# LightBoard2.net
KiCad netlist of a schematic drawn in EAGLE
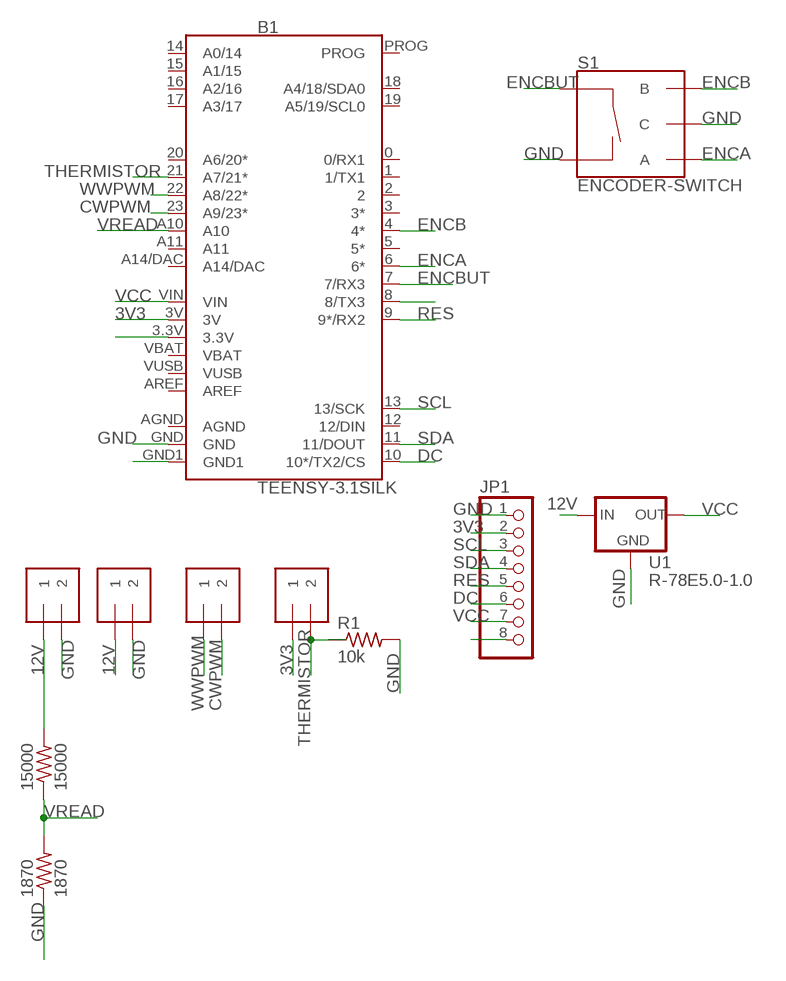
[diagram p0: schematic, sheet 1]

(export (version "E")
  (design (tool "Eeschema 10.0.6"))
  (components
    (comp (ref "1870")
      (value "1870")
      (footprint "eagle-import:0204_5")
      (libsource (lib "eagle-import") (part "R-US_0204/5"))
    )
    (comp (ref "15000")
      (value "15000")
      (footprint "eagle-import:0204_5")
      (libsource (lib "eagle-import") (part "R-US_0204/5"))
    )
    (comp (ref "B1")
      (value "TEENSY-3.1SILK")
      (footprint "eagle-import:TEENSY-3.1")
      (libsource (lib "eagle-import") (part "TEENSY-3.1SILK"))
    )
    (comp (ref "J1")
      (value "1X2-3.5MM")
      (footprint "eagle-import:1X2-3.5MM")
      (libsource (lib "eagle-import") (part "1X2-3.5MM"))
    )
    (comp (ref "J2")
      (value "1X2-3.5MM")
      (footprint "eagle-import:1X2-3.5MM")
      (libsource (lib "eagle-import") (part "1X2-3.5MM"))
    )
    (comp (ref "J3")
      (value "1X2-3.5MM")
      (footprint "eagle-import:1X2-3.5MM")
      (libsource (lib "eagle-import") (part "1X2-3.5MM"))
    )
    (comp (ref "J5")
      (value "1X2-3.5MM")
      (footprint "eagle-import:1X2-3.5MM")
      (libsource (lib "eagle-import") (part "1X2-3.5MM"))
    )
    (comp (ref "JP1")
      (value "PINHD-1X8LOCK")
      (footprint "eagle-import:1X08-LOCK")
      (libsource (lib "eagle-import") (part "PINHD-1X8LOCK"))
    )
    (comp (ref "R1")
      (value "10k")
      (footprint "eagle-import:0204_5")
      (libsource (lib "eagle-import") (part "R-US_0204/5"))
    )
    (comp (ref "S1")
      (value "ENCODER-SWITCH")
      (footprint "eagle-import:ROTARY_ENC_PLAIN")
      (libsource (lib "eagle-import") (part "ENCODER-SWITCH"))
    )
    (comp (ref "U1")
      (value "R-78E5.0-1.0")
      (footprint "eagle-import:DC-DC_CONVERTER_78XX")
      (libsource (lib "eagle-import") (part "R-78E5.0-1.0"))
    )
  )
  (nets
    (net (code "1") (name "/3V3") (class "Default")
      (node (ref "B1") (pin "3V") (pinfunction "3V_3V") (pintype "power_in"))
      (node (ref "J3") (pin "1") (pinfunction "1_1") (pintype "passive"))
      (node (ref "JP1") (pin "2") (pinfunction "2_2") (pintype "passive"))
    )
    (net (code "2") (name "/12V") (class "Default")
      (node (ref "15000") (pin "2") (pinfunction "2_2") (pintype "passive"))
      (node (ref "J2") (pin "1") (pinfunction "1_1") (pintype "passive"))
      (node (ref "J5") (pin "1") (pinfunction "1_1") (pintype "passive"))
      (node (ref "U1") (pin "VIN") (pinfunction "IN_VIN") (pintype "input"))
    )
    (net (code "3") (name "/AGND") (class "Default")
      (node (ref "B1") (pin "AGND") (pinfunction "AGND_AGND") (pintype "power_in"))
    )
    (net (code "4") (name "/CWPWM") (class "Default")
      (node (ref "B1") (pin "23") (pinfunction "A9/23*_23") (pintype "bidirectional"))
      (node (ref "J1") (pin "2") (pinfunction "2_2") (pintype "passive"))
    )
    (net (code "5") (name "/DC") (class "Default")
      (node (ref "B1") (pin "10") (pinfunction "10*/TX2/CS_10") (pintype "bidirectional"))
      (node (ref "JP1") (pin "6") (pinfunction "6_6") (pintype "passive"))
    )
    (net (code "6") (name "/ENCA") (class "Default")
      (node (ref "B1") (pin "6") (pinfunction "6*_6") (pintype "bidirectional"))
      (node (ref "S1") (pin "A") (pinfunction "A_A") (pintype "bidirectional"))
    )
    (net (code "7") (name "/ENCB") (class "Default")
      (node (ref "B1") (pin "4") (pinfunction "4*_4") (pintype "bidirectional"))
      (node (ref "S1") (pin "B") (pinfunction "B_B") (pintype "bidirectional"))
    )
    (net (code "8") (name "/ENCBUT") (class "Default")
      (node (ref "B1") (pin "7") (pinfunction "7/RX3_7") (pintype "bidirectional"))
      (node (ref "S1") (pin "SW+") (pinfunction "SW+_SW+") (pintype "bidirectional"))
    )
    (net (code "9") (name "/GND") (class "Default")
      (node (ref "1870") (pin "1") (pinfunction "1_1") (pintype "passive"))
      (node (ref "B1") (pin "GND") (pinfunction "GND_GND") (pintype "power_in"))
      (node (ref "B1") (pin "GND1") (pinfunction "GND1_GND1") (pintype "power_in"))
      (node (ref "J2") (pin "2") (pinfunction "2_2") (pintype "passive"))
      (node (ref "J5") (pin "2") (pinfunction "2_2") (pintype "passive"))
      (node (ref "JP1") (pin "1") (pinfunction "1_1") (pintype "passive"))
      (node (ref "R1") (pin "2") (pinfunction "2_2") (pintype "passive"))
      (node (ref "S1") (pin "C") (pinfunction "C_C") (pintype "bidirectional"))
      (node (ref "S1") (pin "SW-") (pinfunction "SW-_SW-") (pintype "bidirectional"))
      (node (ref "U1") (pin "GND") (pinfunction "GND_GND") (pintype "input"))
    )
    (net (code "10") (name "/RES") (class "Default")
      (node (ref "B1") (pin "9") (pinfunction "9*/RX2_9") (pintype "bidirectional"))
      (node (ref "JP1") (pin "5") (pinfunction "5_5") (pintype "passive"))
    )
    (net (code "11") (name "/SCL") (class "Default")
      (node (ref "B1") (pin "13") (pinfunction "13/SCK_13") (pintype "bidirectional"))
      (node (ref "JP1") (pin "3") (pinfunction "3_3") (pintype "passive"))
    )
    (net (code "12") (name "/SDA") (class "Default")
      (node (ref "B1") (pin "11") (pinfunction "11/DOUT_11") (pintype "bidirectional"))
      (node (ref "JP1") (pin "4") (pinfunction "4_4") (pintype "passive"))
    )
    (net (code "13") (name "/THERMISTOR") (class "Default")
      (node (ref "B1") (pin "21") (pinfunction "A7/21*_21") (pintype "bidirectional"))
      (node (ref "J3") (pin "2") (pinfunction "2_2") (pintype "passive"))
      (node (ref "R1") (pin "1") (pinfunction "1_1") (pintype "passive"))
    )
    (net (code "14") (name "/VBAT") (class "Default")
      (node (ref "B1") (pin "VBAT") (pinfunction "VBAT_VBAT") (pintype "power_in"))
    )
    (net (code "15") (name "/VCC") (class "Default")
      (node (ref "B1") (pin "VIN") (pinfunction "VIN_VIN") (pintype "power_in"))
      (node (ref "JP1") (pin "7") (pinfunction "7_7") (pintype "passive"))
      (node (ref "U1") (pin "VOUT") (pinfunction "OUT_VOUT") (pintype "passive"))
    )
    (net (code "16") (name "/VREAD") (class "Default")
      (node (ref "15000") (pin "1") (pinfunction "1_1") (pintype "passive"))
      (node (ref "1870") (pin "2") (pinfunction "2_2") (pintype "passive"))
      (node (ref "B1") (pin "A10") (pinfunction "A10_A10") (pintype "bidirectional"))
    )
    (net (code "17") (name "/VUSB") (class "Default")
      (node (ref "B1") (pin "VUSB") (pinfunction "VUSB_VUSB") (pintype "power_in"))
    )
    (net (code "18") (name "/WWPWM") (class "Default")
      (node (ref "B1") (pin "22") (pinfunction "A8/22*_22") (pintype "bidirectional"))
      (node (ref "J1") (pin "1") (pinfunction "1_1") (pintype "passive"))
    )
    (net (code "19") (name "unconnected-(B1-0{slash}RX1-Pad0)") (class "Default")
      (node (ref "B1") (pin "0") (pinfunction "0/RX1_0") (pintype "bidirectional"))
    )
    (net (code "20") (name "unconnected-(B1-1{slash}TX1-Pad1)") (class "Default")
      (node (ref "B1") (pin "1") (pinfunction "1/TX1_1") (pintype "bidirectional"))
    )
    (net (code "21") (name "unconnected-(B1-3*-Pad3)") (class "Default")
      (node (ref "B1") (pin "3") (pinfunction "3*_3") (pintype "bidirectional"))
    )
    (net (code "22") (name "unconnected-(B1-5*-Pad5)") (class "Default")
      (node (ref "B1") (pin "5") (pinfunction "5*_5") (pintype "bidirectional"))
    )
    (net (code "23") (name "unconnected-(B1-8{slash}TX3-Pad8)") (class "Default")
      (node (ref "B1") (pin "8") (pinfunction "8/TX3_8") (pintype "bidirectional"))
    )
    (net (code "24") (name "unconnected-(B1-12{slash}DIN-Pad12)") (class "Default")
      (node (ref "B1") (pin "12") (pinfunction "12/DIN_12") (pintype "bidirectional"))
    )
    (net (code "25") (name "unconnected-(B1-A0{slash}14-Pad14)") (class "Default")
      (node (ref "B1") (pin "14") (pinfunction "A0/14_14") (pintype "bidirectional"))
    )
    (net (code "26") (name "unconnected-(B1-A1{slash}15-Pad15)") (class "Default")
      (node (ref "B1") (pin "15") (pinfunction "A1/15_15") (pintype "bidirectional"))
    )
    (net (code "27") (name "unconnected-(B1-A2{slash}16-Pad16)") (class "Default")
      (node (ref "B1") (pin "16") (pinfunction "A2/16_16") (pintype "bidirectional"))
    )
    (net (code "28") (name "unconnected-(B1-A3{slash}17-Pad17)") (class "Default")
      (node (ref "B1") (pin "17") (pinfunction "A3/17_17") (pintype "bidirectional"))
    )
    (net (code "29") (name "unconnected-(B1-A4{slash}18{slash}SDA0-Pad18)") (class "Default")
      (node (ref "B1") (pin "18") (pinfunction "A4/18/SDA0_18") (pintype "bidirectional"))
    )
    (net (code "30") (name "unconnected-(B1-A5{slash}19{slash}SCL0-Pad19)") (class "Default")
      (node (ref "B1") (pin "19") (pinfunction "A5/19/SCL0_19") (pintype "bidirectional"))
    )
    (net (code "31") (name "unconnected-(B1-A6{slash}20*-Pad20)") (class "Default")
      (node (ref "B1") (pin "20") (pinfunction "A6/20*_20") (pintype "bidirectional"))
    )
    (net (code "32") (name "unconnected-(B1-Pad2)") (class "Default")
      (node (ref "B1") (pin "2") (pinfunction "2_2") (pintype "bidirectional"))
    )
    (net (code "33") (name "unconnected-(B1-Pad3.3V)") (class "Default")
      (node (ref "B1") (pin "3.3V") (pinfunction "3.3V_3.3V") (pintype "power_in"))
    )
    (net (code "34") (name "unconnected-(B1-PadA11)") (class "Default")
      (node (ref "B1") (pin "A11") (pinfunction "A11_A11") (pintype "bidirectional"))
    )
    (net (code "35") (name "unconnected-(B1-PadA14{slash}DAC)") (class "Default")
      (node (ref "B1") (pin "A14/DAC") (pinfunction "A14/DAC_A14/DAC") (pintype "bidirectional"))
    )
    (net (code "36") (name "unconnected-(B1-PadAREF)") (class "Default")
      (node (ref "B1") (pin "AREF") (pinfunction "AREF_AREF") (pintype "bidirectional"))
    )
    (net (code "37") (name "unconnected-(B1-PadPROG)") (class "Default")
      (node (ref "B1") (pin "PROG") (pinfunction "PROG_PROG") (pintype "bidirectional"))
    )
    (net (code "38") (name "unconnected-(JP1-Pad8)") (class "Default")
      (node (ref "JP1") (pin "8") (pinfunction "8_8") (pintype "passive"))
    )
  )
)
